# integratorLoop.net
KiCad netlist of a schematic drawn in Altium Designer
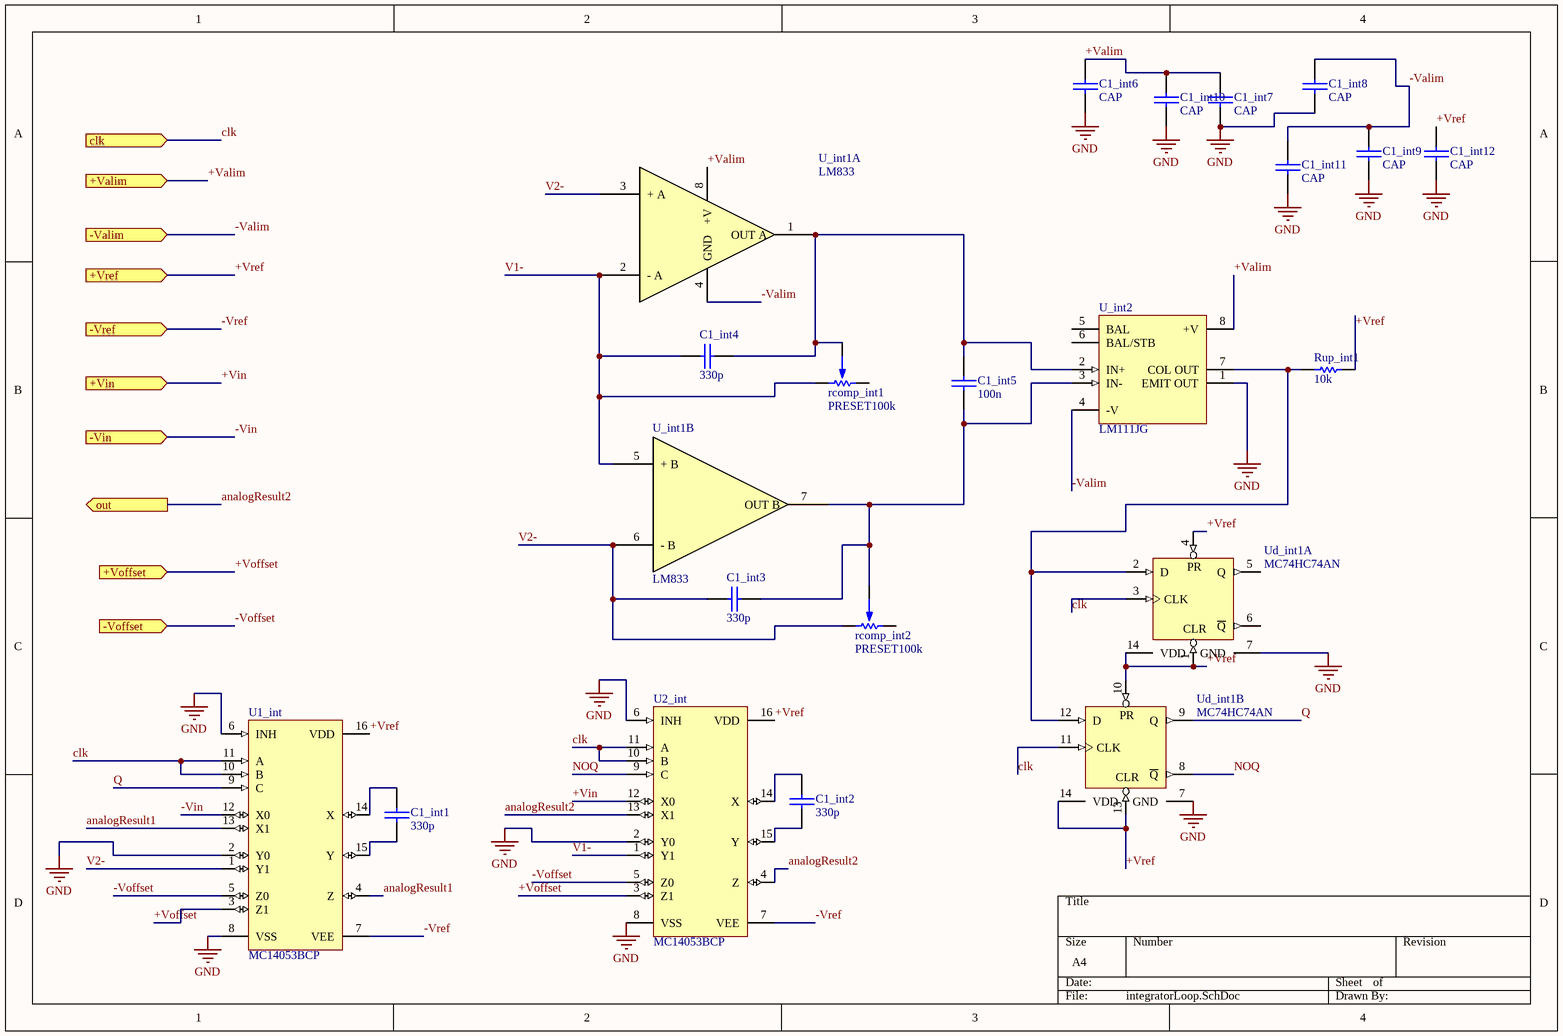
[diagram p0: integratorLoop.SchDoc]

(export (version "E")
  (design (tool "Eeschema 10.0.6"))
  (components
    (comp (ref "C1_int1") (value "330p") (footprint "CAP200") (libsource (lib "LIBEBAL") (part "CAP")))
    (comp (ref "C1_int2") (value "330p") (footprint "CAP200") (libsource (lib "LIBEBAL") (part "CAP")))
    (comp (ref "C1_int3") (value "330p") (footprint "CAP200") (libsource (lib "LIBEBAL") (part "CAP")))
    (comp (ref "C1_int4") (value "330p") (footprint "CAP200") (libsource (lib "LIBEBAL") (part "CAP")))
    (comp (ref "C1_int5") (value "100n") (footprint "CAP200") (libsource (lib "LIBEBAL") (part "CAP")))
    (comp (ref "C1_int6") (value "CAP") (footprint "CAP200") (libsource (lib "LIBEBAL") (part "CAP")))
    (comp (ref "C1_int7") (value "CAP") (footprint "CAP200") (libsource (lib "LIBEBAL") (part "CAP")))
    (comp (ref "C1_int8") (value "CAP") (footprint "CAP200") (libsource (lib "LIBEBAL") (part "CAP")))
    (comp (ref "C1_int9") (value "CAP") (footprint "CAP200") (libsource (lib "LIBEBAL") (part "CAP")))
    (comp (ref "C1_int10") (value "CAP") (footprint "CAP200") (libsource (lib "LIBEBAL") (part "CAP")))
    (comp (ref "C1_int11") (value "CAP") (footprint "CAP200") (libsource (lib "LIBEBAL") (part "CAP")))
    (comp (ref "C1_int12") (value "CAP") (footprint "CAP200") (libsource (lib "LIBEBAL") (part "CAP")))
    (comp (ref "rcomp_int1")
      (value "PRESET100k")
      (footprint "PRESET V")
      (libsource (lib "LIBEBAL") (part "PRESET"))
    )
    (comp (ref "rcomp_int2")
      (value "PRESET100k")
      (footprint "PRESET V")
      (libsource (lib "LIBEBAL") (part "PRESET"))
    )
    (comp (ref "Rup_int1") (value "10k") (footprint "RES300") (libsource (lib "LIBEBAL") (part "RES")))
    (comp (ref "U1_int")
      (value "MC14053BCP")
      (footprint "648-08")
      (description "Triple 2-Channel Analog Multiplexer/Demultiplexer")
      (fields (field (name "PUBLISHER") "Altium Limited"))
      (libsource (lib "ON Semi Logic Multiplexer") (part "MC14053BCP"))
    )
    (comp (ref "U2_int")
      (value "MC14053BCP")
      (footprint "648-08")
      (description "Triple 2-Channel Analog Multiplexer/Demultiplexer")
      (fields (field (name "PUBLISHER") "Altium Limited"))
      (libsource (lib "ON Semi Logic Multiplexer") (part "MC14053BCP"))
    )
    (comp (ref "Ud_int1")
      (value "MC74HC74AN")
      (footprint "646-06")
      (description "Dual D-Type Flip-Flop with Set and Reset")
      (fields (field (name "PUBLISHER") "Altium Limited"))
      (libsource (lib "ON Semi Logic Flip-Flop") (part "MC74HC74AN"))
    )
    (comp (ref "U_int1")
      (value "LM833")
      (footprint "DIP8")
      (description "Dual Audio Operational Amplifier")
      (libsource (lib "LIBEBAL") (part "LM833"))
    )
    (comp (ref "U_int2")
      (value "LM111JG")
      (footprint "JG008")
      (description "Differential Comparator with Strobe")
      (fields (field (name "PUBLISHER") "Altium Limited"))
      (libsource (lib "TI Analog Comparator") (part "LM111JG"))
    )
  )
  (nets
    (net (code "1") (name "/+Valim") (class "Default")
      (node (ref "C1_int10") (pin "1") (pinfunction "1_1") (pintype "passive"))
      (node (ref "C1_int6") (pin "1") (pinfunction "1_1") (pintype "passive"))
      (node (ref "C1_int7") (pin "1") (pinfunction "1_1") (pintype "passive"))
      (node (ref "U_int1") (pin "8") (pinfunction "+V_8") (pintype "passive"))
      (node (ref "U_int2") (pin "8") (pinfunction "+V_8") (pintype "power_in"))
    )
    (net (code "2") (name "/+Vin") (class "Default")
      (node (ref "U2_int") (pin "12") (pinfunction "X0_12") (pintype "bidirectional"))
    )
    (net (code "3") (name "/+Voffset") (class "Default")
      (node (ref "U1_int") (pin "3") (pinfunction "Z1_3") (pintype "bidirectional"))
      (node (ref "U2_int") (pin "3") (pinfunction "Z1_3") (pintype "bidirectional"))
    )
    (net (code "4") (name "/+Vref") (class "Default")
      (node (ref "C1_int12") (pin "1") (pinfunction "1_1") (pintype "passive"))
      (node (ref "Rup_int1") (pin "2") (pinfunction "2_2") (pintype "passive"))
      (node (ref "U1_int") (pin "16") (pinfunction "VDD_16") (pintype "power_in"))
      (node (ref "U2_int") (pin "16") (pinfunction "VDD_16") (pintype "power_in"))
      (node (ref "Ud_int1") (pin "1") (pinfunction "CLR_1") (pintype "input"))
      (node (ref "Ud_int1") (pin "10") (pinfunction "PR_10") (pintype "input"))
      (node (ref "Ud_int1") (pin "13") (pinfunction "CLR_13") (pintype "input"))
      (node (ref "Ud_int1") (pin "14") (pinfunction "VDD_14") (pintype "power_in"))
      (node (ref "Ud_int1") (pin "4") (pinfunction "PR_4") (pintype "input"))
    )
    (net (code "5") (name "/-Valim") (class "Default")
      (node (ref "C1_int11") (pin "1") (pinfunction "1_1") (pintype "passive"))
      (node (ref "C1_int8") (pin "1") (pinfunction "1_1") (pintype "passive"))
      (node (ref "C1_int9") (pin "1") (pinfunction "1_1") (pintype "passive"))
      (node (ref "U_int1") (pin "4") (pinfunction "GND_4") (pintype "passive"))
      (node (ref "U_int2") (pin "4") (pinfunction "-V_4") (pintype "power_in"))
    )
    (net (code "6") (name "/-Vin") (class "Default")
      (node (ref "U1_int") (pin "12") (pinfunction "X0_12") (pintype "bidirectional"))
    )
    (net (code "7") (name "/-Voffset") (class "Default")
      (node (ref "U1_int") (pin "5") (pinfunction "Z0_5") (pintype "bidirectional"))
      (node (ref "U2_int") (pin "5") (pinfunction "Z0_5") (pintype "bidirectional"))
    )
    (net (code "8") (name "/-Vref") (class "Default")
      (node (ref "U1_int") (pin "7") (pinfunction "VEE_7") (pintype "power_in"))
      (node (ref "U2_int") (pin "7") (pinfunction "VEE_7") (pintype "power_in"))
    )
    (net (code "9") (name "/NOQ") (class "Default")
      (node (ref "U2_int") (pin "9") (pinfunction "C_9") (pintype "input"))
      (node (ref "Ud_int1") (pin "8") (pinfunction "~{Q}_8") (pintype "output"))
    )
    (net (code "10") (name "/Q") (class "Default")
      (node (ref "U1_int") (pin "9") (pinfunction "C_9") (pintype "input"))
      (node (ref "Ud_int1") (pin "9") (pinfunction "Q_9") (pintype "output"))
    )
    (net (code "11") (name "/V1-") (class "Default")
      (node (ref "C1_int4") (pin "1") (pinfunction "1_1") (pintype "passive"))
      (node (ref "U2_int") (pin "1") (pinfunction "Y1_1") (pintype "bidirectional"))
      (node (ref "U_int1") (pin "2") (pinfunction "-_A_2") (pintype "passive"))
      (node (ref "U_int1") (pin "5") (pinfunction "+_B_5") (pintype "passive"))
      (node (ref "rcomp_int1") (pin "1") (pinfunction "1_1") (pintype "passive"))
    )
    (net (code "12") (name "/V2-") (class "Default")
      (node (ref "C1_int3") (pin "1") (pinfunction "1_1") (pintype "passive"))
      (node (ref "U1_int") (pin "1") (pinfunction "Y1_1") (pintype "bidirectional"))
      (node (ref "U_int1") (pin "3") (pinfunction "+_A_3") (pintype "passive"))
      (node (ref "U_int1") (pin "6") (pinfunction "-_B_6") (pintype "passive"))
      (node (ref "rcomp_int2") (pin "1") (pinfunction "1_1") (pintype "passive"))
    )
    (net (code "13") (name "/analogResult1") (class "Default")
      (node (ref "U1_int") (pin "13") (pinfunction "X1_13") (pintype "bidirectional"))
      (node (ref "U1_int") (pin "4") (pinfunction "Z_4") (pintype "bidirectional"))
    )
    (net (code "14") (name "/analogResult2") (class "Default")
      (node (ref "U2_int") (pin "13") (pinfunction "X1_13") (pintype "bidirectional"))
      (node (ref "U2_int") (pin "4") (pinfunction "Z_4") (pintype "bidirectional"))
    )
    (net (code "15") (name "/clk") (class "Default")
      (node (ref "U1_int") (pin "10") (pinfunction "B_10") (pintype "input"))
      (node (ref "U1_int") (pin "11") (pinfunction "A_11") (pintype "input"))
      (node (ref "U2_int") (pin "10") (pinfunction "B_10") (pintype "input"))
      (node (ref "U2_int") (pin "11") (pinfunction "A_11") (pintype "input"))
      (node (ref "Ud_int1") (pin "11") (pinfunction "CLK_11") (pintype "input"))
      (node (ref "Ud_int1") (pin "3") (pinfunction "CLK_3") (pintype "input"))
    )
    (net (code "16") (name "GND") (class "Default")
      (node (ref "C1_int10") (pin "2") (pinfunction "2_2") (pintype "passive"))
      (node (ref "C1_int11") (pin "2") (pinfunction "2_2") (pintype "passive"))
      (node (ref "C1_int12") (pin "2") (pinfunction "2_2") (pintype "passive"))
      (node (ref "C1_int6") (pin "2") (pinfunction "2_2") (pintype "passive"))
      (node (ref "C1_int7") (pin "2") (pinfunction "2_2") (pintype "passive"))
      (node (ref "C1_int8") (pin "2") (pinfunction "2_2") (pintype "passive"))
      (node (ref "C1_int9") (pin "2") (pinfunction "2_2") (pintype "passive"))
      (node (ref "U1_int") (pin "2") (pinfunction "Y0_2") (pintype "bidirectional"))
      (node (ref "U1_int") (pin "6") (pinfunction "INH_6") (pintype "input"))
      (node (ref "U1_int") (pin "8") (pinfunction "VSS_8") (pintype "power_in"))
      (node (ref "U2_int") (pin "2") (pinfunction "Y0_2") (pintype "bidirectional"))
      (node (ref "U2_int") (pin "6") (pinfunction "INH_6") (pintype "input"))
      (node (ref "U2_int") (pin "8") (pinfunction "VSS_8") (pintype "power_in"))
      (node (ref "U_int2") (pin "1") (pinfunction "EMIT_OUT_1") (pintype "open_emitter"))
      (node (ref "Ud_int1") (pin "7") (pinfunction "GND_7") (pintype "power_in"))
    )
    (net (code "17") (name "Net-(U1_int-X)") (class "Default")
      (node (ref "C1_int1") (pin "1") (pinfunction "1_1") (pintype "passive"))
      (node (ref "U1_int") (pin "14") (pinfunction "X_14") (pintype "bidirectional"))
    )
    (net (code "18") (name "Net-(U1_int-Y)") (class "Default")
      (node (ref "C1_int1") (pin "2") (pinfunction "2_2") (pintype "passive"))
      (node (ref "U1_int") (pin "15") (pinfunction "Y_15") (pintype "bidirectional"))
    )
    (net (code "19") (name "Net-(U2_int-X)") (class "Default")
      (node (ref "C1_int2") (pin "1") (pinfunction "1_1") (pintype "passive"))
      (node (ref "U2_int") (pin "14") (pinfunction "X_14") (pintype "bidirectional"))
    )
    (net (code "20") (name "Net-(U2_int-Y)") (class "Default")
      (node (ref "C1_int2") (pin "2") (pinfunction "2_2") (pintype "passive"))
      (node (ref "U2_int") (pin "15") (pinfunction "Y_15") (pintype "bidirectional"))
    )
    (net (code "21") (name "Net-(U_int1A-OUT_A)") (class "Default")
      (node (ref "C1_int4") (pin "2") (pinfunction "2_2") (pintype "passive"))
      (node (ref "C1_int5") (pin "1") (pinfunction "1_1") (pintype "passive"))
      (node (ref "U_int1") (pin "1") (pinfunction "OUT_A_1") (pintype "passive"))
      (node (ref "U_int2") (pin "2") (pinfunction "IN+_2") (pintype "input"))
      (node (ref "rcomp_int1") (pin "2") (pinfunction "2_2") (pintype "passive"))
    )
    (net (code "22") (name "Net-(U_int1B-OUT_B)") (class "Default")
      (node (ref "C1_int3") (pin "2") (pinfunction "2_2") (pintype "passive"))
      (node (ref "C1_int5") (pin "2") (pinfunction "2_2") (pintype "passive"))
      (node (ref "U_int1") (pin "7") (pinfunction "OUT_B_7") (pintype "passive"))
      (node (ref "U_int2") (pin "3") (pinfunction "IN-_3") (pintype "input"))
      (node (ref "rcomp_int2") (pin "2") (pinfunction "2_2") (pintype "passive"))
    )
    (net (code "23") (name "Net-(U_int2-COL_OUT)") (class "Default")
      (node (ref "Rup_int1") (pin "1") (pinfunction "1_1") (pintype "passive"))
      (node (ref "U_int2") (pin "7") (pinfunction "COL_OUT_7") (pintype "open_collector"))
      (node (ref "Ud_int1") (pin "12") (pinfunction "D_12") (pintype "input"))
      (node (ref "Ud_int1") (pin "2") (pinfunction "D_2") (pintype "input"))
    )
    (net (code "24") (name "unconnected-(U_int2-BAL-Pad5)") (class "Default")
      (node (ref "U_int2") (pin "5") (pinfunction "BAL_5") (pintype "passive"))
    )
    (net (code "25") (name "unconnected-(U_int2-BAL{slash}STB-Pad6)") (class "Default")
      (node (ref "U_int2") (pin "6") (pinfunction "BAL/STB_6") (pintype "passive"))
    )
    (net (code "26") (name "unconnected-(Ud_int1A-Q-Pad5)") (class "Default")
      (node (ref "Ud_int1") (pin "5") (pinfunction "Q_5") (pintype "output"))
    )
    (net (code "27") (name "unconnected-(Ud_int1A-~{Q}-Pad6)") (class "Default")
      (node (ref "Ud_int1") (pin "6") (pinfunction "~{Q}_6") (pintype "output"))
    )
    (net (code "28") (name "unconnected-(rcomp_int1-Pad3)") (class "Default")
      (node (ref "rcomp_int1") (pin "3") (pinfunction "3_3") (pintype "passive"))
    )
    (net (code "29") (name "unconnected-(rcomp_int2-Pad3)") (class "Default")
      (node (ref "rcomp_int2") (pin "3") (pinfunction "3_3") (pintype "passive"))
    )
  )
)
